# beovox-poe.net
KiCad netlist of a schematic drawn in Altium Designer
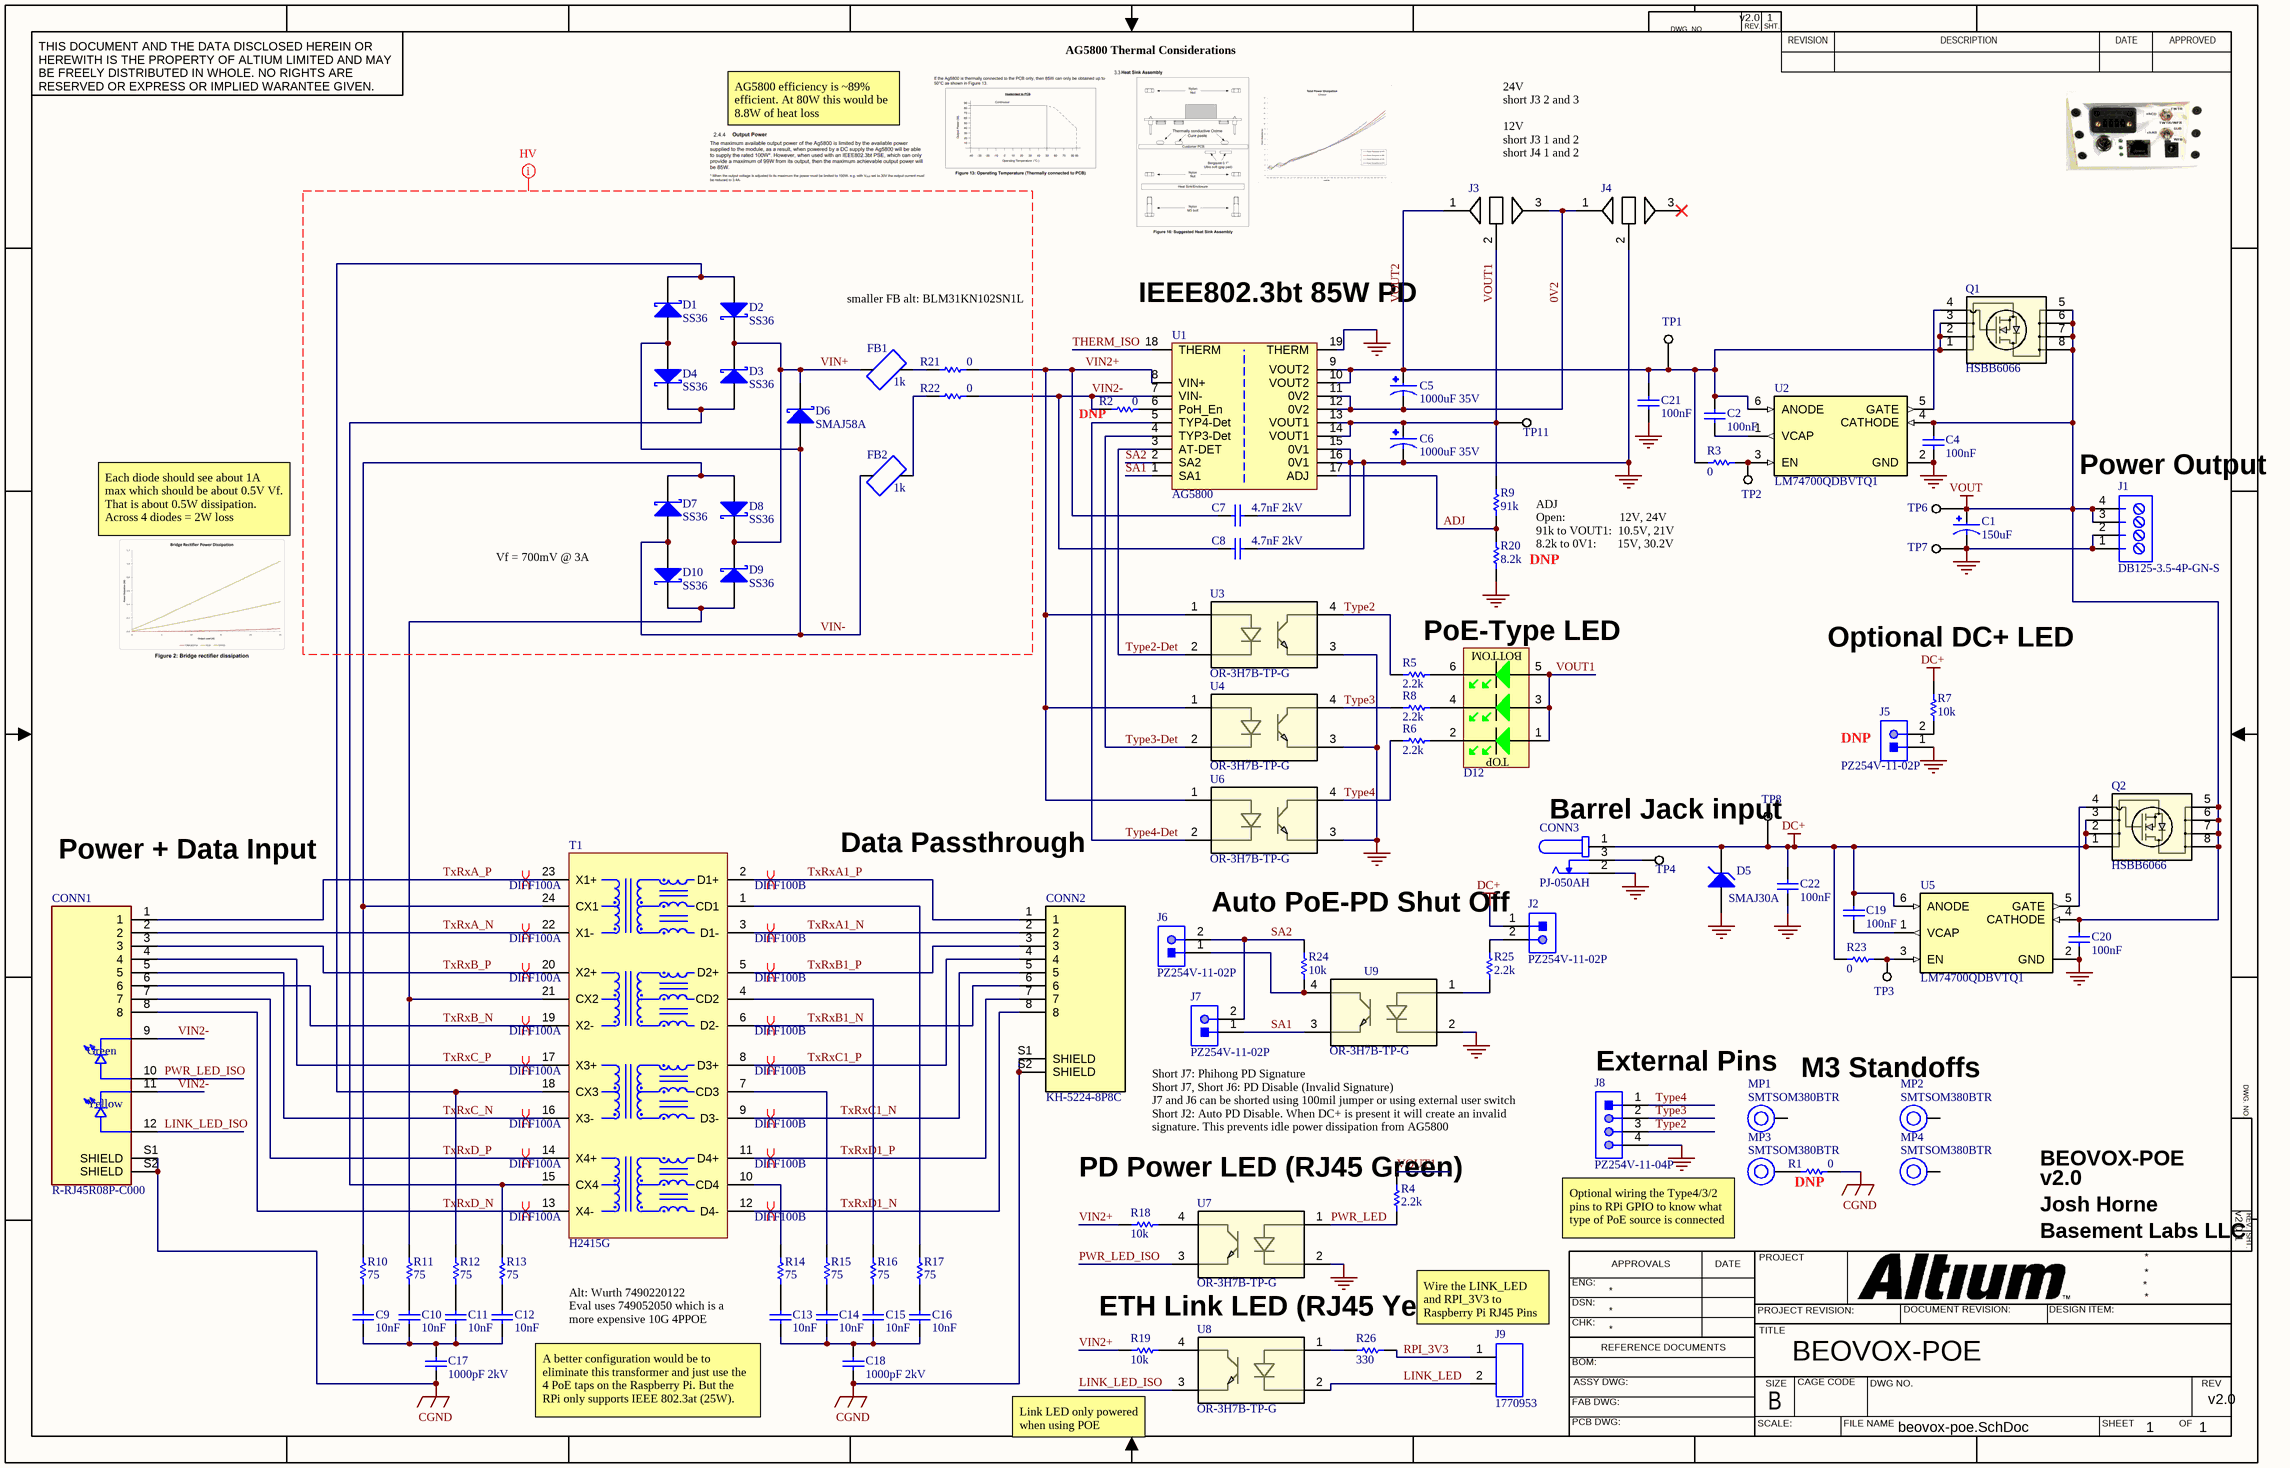
[diagram p0: beovox-poe.SchDoc]

(export (version "E")
  (design (tool "Eeschema 10.0.6"))
  (components
    (comp (ref "C1")
      (value "150uF")
      (footprint "CAP_CAN_10D_16H_THT")
      (description "150uF 80V Aluminum Electrolytic Capacitors Through Hole,D10xL16mm 3000hrs@105℃")
      (fields
        (field (name "MANUFACTURER") "BERYL Electronic Tech")
        (field (name "MANUFACTURER PART NUMBER") "RC080M151LO10*16TH-2A1Et")
      )
      (libsource (lib "josh-lib") (part "RC080M151LO10*16TH-2A1Et"))
    )
    (comp (ref "C2")
      (value "100nF")
      (footprint "CAP_0603_SK")
      (description "Multilayer Ceramic Capacitor, CC Series, 0.1 - F, - 10%, X7R, 50 V, 0603 [1608 Metric]")
      (fields
        (field (name "MANUFACTURER") "Yageo")
        (field (name "MANUFACTURER PART NUMBER") "CC0603KRX7R9BB104")
      )
      (libsource (lib "josh-lib") (part "C0603 100nF 50V X7R 10%"))
    )
    (comp (ref "C4")
      (value "100nF")
      (footprint "CAP_0603_SK")
      (description "Multilayer Ceramic Capacitor, CC Series, 0.1 - F, - 10%, X7R, 50 V, 0603 [1608 Metric]")
      (fields
        (field (name "MANUFACTURER") "Yageo")
        (field (name "MANUFACTURER PART NUMBER") "CC0603KRX7R9BB104")
      )
      (libsource (lib "josh-lib") (part "C0603 100nF 50V X7R 10%"))
    )
    (comp (ref "C5")
      (value "1000uF 35V")
      (footprint "CAP_TH_5_10X20")
      (description "1000uF 35V ±20% Plugin,D10xL20mm Aluminum Electrolytic Capacitors - Leaded ROHS")
      (fields
        (field (name "MANUFACTURER") "AISHI")
        (field (name "MANUFACTURER PART NUMBER") "ERR1VM102G20OT")
      )
      (libsource (lib "josh-lib") (part "ERR1VM102G20OT"))
    )
    (comp (ref "C6")
      (value "1000uF 35V")
      (footprint "CAP_TH_5_10X20")
      (description "1000uF 35V ±20% Plugin,D10xL20mm Aluminum Electrolytic Capacitors - Leaded ROHS")
      (fields
        (field (name "MANUFACTURER") "AISHI")
        (field (name "MANUFACTURER PART NUMBER") "ERR1VM102G20OT")
      )
      (libsource (lib "josh-lib") (part "ERR1VM102G20OT"))
    )
    (comp (ref "C7")
      (value "4.7nF 2kV")
      (footprint "CAP_1206_SK")
      (description "2kV 4700pF X7R ±10% 1206 Multilayer Ceramic Capacitors MLCC - SMD/SMT ROHS")
      (fields
        (field (name "MANUFACTURER") "FH (Guangdong Fenghua Advanced Tech)")
        (field (name "MANUFACTURER PART NUMBER") "1206B472K202NT")
      )
      (libsource (lib "josh-lib") (part "1206B472K202NT"))
    )
    (comp (ref "C8")
      (value "4.7nF 2kV")
      (footprint "CAP_1206_SK")
      (description "2kV 4700pF X7R ±10% 1206 Multilayer Ceramic Capacitors MLCC - SMD/SMT ROHS")
      (fields
        (field (name "MANUFACTURER") "FH (Guangdong Fenghua Advanced Tech)")
        (field (name "MANUFACTURER PART NUMBER") "1206B472K202NT")
      )
      (libsource (lib "josh-lib") (part "1206B472K202NT"))
    )
    (comp (ref "C9")
      (value "10nF")
      (footprint "CAP_0603_SK")
      (description "Multilayer Ceramic Capacitor, 0.01 F, 10%, X7R, 100 V, 0603 [1608 Metric] Rohs Compliant: Yes")
      (fields
        (field (name "MANUFACTURER") "Walsin Technologies")
        (field (name "MANUFACTURER PART NUMBER") "0603B103K101CT")
      )
      (libsource (lib "josh-lib") (part "0603B103K101CT"))
    )
    (comp (ref "C10")
      (value "10nF")
      (footprint "CAP_0603_SK")
      (description "Multilayer Ceramic Capacitor, 0.01 F, 10%, X7R, 100 V, 0603 [1608 Metric] Rohs Compliant: Yes")
      (fields
        (field (name "MANUFACTURER") "Walsin Technologies")
        (field (name "MANUFACTURER PART NUMBER") "0603B103K101CT")
      )
      (libsource (lib "josh-lib") (part "0603B103K101CT"))
    )
    (comp (ref "C11")
      (value "10nF")
      (footprint "CAP_0603_SK")
      (description "Multilayer Ceramic Capacitor, 0.01 F, 10%, X7R, 100 V, 0603 [1608 Metric] Rohs Compliant: Yes")
      (fields
        (field (name "MANUFACTURER") "Walsin Technologies")
        (field (name "MANUFACTURER PART NUMBER") "0603B103K101CT")
      )
      (libsource (lib "josh-lib") (part "0603B103K101CT"))
    )
    (comp (ref "C12")
      (value "10nF")
      (footprint "CAP_0603_SK")
      (description "Multilayer Ceramic Capacitor, 0.01 F, 10%, X7R, 100 V, 0603 [1608 Metric] Rohs Compliant: Yes")
      (fields
        (field (name "MANUFACTURER") "Walsin Technologies")
        (field (name "MANUFACTURER PART NUMBER") "0603B103K101CT")
      )
      (libsource (lib "josh-lib") (part "0603B103K101CT"))
    )
    (comp (ref "C13")
      (value "10nF")
      (footprint "CAP_0603_SK")
      (description "Multilayer Ceramic Capacitor, 0.01 F, 10%, X7R, 100 V, 0603 [1608 Metric] Rohs Compliant: Yes")
      (fields
        (field (name "MANUFACTURER") "Walsin Technologies")
        (field (name "MANUFACTURER PART NUMBER") "0603B103K101CT")
      )
      (libsource (lib "josh-lib") (part "0603B103K101CT"))
    )
    (comp (ref "C14")
      (value "10nF")
      (footprint "CAP_0603_SK")
      (description "Multilayer Ceramic Capacitor, 0.01 F, 10%, X7R, 100 V, 0603 [1608 Metric] Rohs Compliant: Yes")
      (fields
        (field (name "MANUFACTURER") "Walsin Technologies")
        (field (name "MANUFACTURER PART NUMBER") "0603B103K101CT")
      )
      (libsource (lib "josh-lib") (part "0603B103K101CT"))
    )
    (comp (ref "C15")
      (value "10nF")
      (footprint "CAP_0603_SK")
      (description "Multilayer Ceramic Capacitor, 0.01 F, 10%, X7R, 100 V, 0603 [1608 Metric] Rohs Compliant: Yes")
      (fields
        (field (name "MANUFACTURER") "Walsin Technologies")
        (field (name "MANUFACTURER PART NUMBER") "0603B103K101CT")
      )
      (libsource (lib "josh-lib") (part "0603B103K101CT"))
    )
    (comp (ref "C16")
      (value "10nF")
      (footprint "CAP_0603_SK")
      (description "Multilayer Ceramic Capacitor, 0.01 F, 10%, X7R, 100 V, 0603 [1608 Metric] Rohs Compliant: Yes")
      (fields
        (field (name "MANUFACTURER") "Walsin Technologies")
        (field (name "MANUFACTURER PART NUMBER") "0603B103K101CT")
      )
      (libsource (lib "josh-lib") (part "0603B103K101CT"))
    )
    (comp (ref "C17")
      (value "1000pF 2kV")
      (footprint "CAP_1206_SK")
      (description "Multilayer Ceramic Capacitor, 1000 pF, 2000 V, ± 10%, X7R, 1206 [3216 Metric]")
      (fields
        (field (name "MANUFACTURER") "Yageo")
        (field (name "MANUFACTURER PART NUMBER") "CC1206KKX7RDBB102")
      )
      (libsource (lib "josh-lib") (part "CC1206KKX7RDBB102"))
    )
    (comp (ref "C18")
      (value "1000pF 2kV")
      (footprint "CAP_1206_SK")
      (description "Multilayer Ceramic Capacitor, 1000 pF, 2000 V, ± 10%, X7R, 1206 [3216 Metric]")
      (fields
        (field (name "MANUFACTURER") "Yageo")
        (field (name "MANUFACTURER PART NUMBER") "CC1206KKX7RDBB102")
      )
      (libsource (lib "josh-lib") (part "CC1206KKX7RDBB102"))
    )
    (comp (ref "C19")
      (value "100nF")
      (footprint "CAP_0603_SK")
      (description "Multilayer Ceramic Capacitor, CC Series, 0.1 - F, - 10%, X7R, 50 V, 0603 [1608 Metric]")
      (fields
        (field (name "MANUFACTURER") "Yageo")
        (field (name "MANUFACTURER PART NUMBER") "CC0603KRX7R9BB104")
      )
      (libsource (lib "josh-lib") (part "C0603 100nF 50V X7R 10%"))
    )
    (comp (ref "C20")
      (value "100nF")
      (footprint "CAP_0603_SK")
      (description "Multilayer Ceramic Capacitor, CC Series, 0.1 - F, - 10%, X7R, 50 V, 0603 [1608 Metric]")
      (fields
        (field (name "MANUFACTURER") "Yageo")
        (field (name "MANUFACTURER PART NUMBER") "CC0603KRX7R9BB104")
      )
      (libsource (lib "josh-lib") (part "C0603 100nF 50V X7R 10%"))
    )
    (comp (ref "C21")
      (value "100nF")
      (footprint "CAP_0603_SK")
      (description "Multilayer Ceramic Capacitor, CC Series, 0.1 - F, - 10%, X7R, 50 V, 0603 [1608 Metric]")
      (fields
        (field (name "MANUFACTURER") "Yageo")
        (field (name "MANUFACTURER PART NUMBER") "CC0603KRX7R9BB104")
      )
      (libsource (lib "josh-lib") (part "C0603 100nF 50V X7R 10%"))
    )
    (comp (ref "C22")
      (value "100nF")
      (footprint "CAP_0603_SK")
      (description "Multilayer Ceramic Capacitor, CC Series, 0.1 - F, - 10%, X7R, 50 V, 0603 [1608 Metric]")
      (fields
        (field (name "MANUFACTURER") "Yageo")
        (field (name "MANUFACTURER PART NUMBER") "CC0603KRX7R9BB104")
      )
      (libsource (lib "josh-lib") (part "C0603 100nF 50V X7R 10%"))
    )
    (comp (ref "CONN1")
      (value "R-RJ45R08P-C000")
      (footprint "R-RJ45R08P-C000")
      (fields (field (name "MANUFACTURER") "Ckmtw"))
      (libsource (lib "josh-lib") (part "R-RJ45R08P-C000"))
    )
    (comp (ref "CONN2")
      (value "KH-5224-8P8C")
      (footprint "CONN_RJ45_KH-5224-8P8C")
      (description "Jack Modular Connector RJ45 Through Hole Shielded")
      (fields (field (name "MANUFACTURER") "Kinghelm"))
      (libsource (lib "josh-lib") (part "KH-5224-8P8C"))
    )
    (comp (ref "CONN3")
      (value "PJ-050AH")
      (footprint "CUI_PJ-050AH")
      (description "2.0 x 6.0 mm, 5.0 A, Horizontal, Through Hole, Pick-n-Place Top, Dc Power Jack Connector")
      (fields (field (name "MANUFACTURER") "Same Sky"))
      (libsource (lib "josh-lib") (part "PJ-050AH"))
    )
    (comp (ref "D1")
      (value "SS36")
      (footprint "DIOD-SMA-2_V")
      (description "60V 700mV@3A 3A SMA(DO-214AC) Schottky Barrier Diodes (SBD) ROHS")
      (fields (field (name "MANUFACTURER") "MDD"))
      (libsource (lib "josh-lib") (part "SS36"))
    )
    (comp (ref "D2")
      (value "SS36")
      (footprint "DIOD-SMA-2_V")
      (description "60V 700mV@3A 3A SMA(DO-214AC) Schottky Barrier Diodes (SBD) ROHS")
      (fields (field (name "MANUFACTURER") "MDD"))
      (libsource (lib "josh-lib") (part "SS36"))
    )
    (comp (ref "D3")
      (value "SS36")
      (footprint "DIOD-SMA-2_V")
      (description "60V 700mV@3A 3A SMA(DO-214AC) Schottky Barrier Diodes (SBD) ROHS")
      (fields (field (name "MANUFACTURER") "MDD"))
      (libsource (lib "josh-lib") (part "SS36"))
    )
    (comp (ref "D4")
      (value "SS36")
      (footprint "DIOD-SMA-2_V")
      (description "60V 700mV@3A 3A SMA(DO-214AC) Schottky Barrier Diodes (SBD) ROHS")
      (fields (field (name "MANUFACTURER") "MDD"))
      (libsource (lib "josh-lib") (part "SS36"))
    )
    (comp (ref "D5")
      (value "SMAJ30A")
      (footprint "DIOD-B360A_V")
      (description "Diode TVS Single Uni-Dir 30V 400W 2-Pin SMA")
      (fields (field (name "MANUFACTURER") "Littelfuse"))
      (libsource (lib "josh-lib") (part "SMAJ30A"))
    )
    (comp (ref "D6")
      (value "SMAJ58A")
      (footprint "DIOD-SMA-2_V")
      (description "4.3A 400W 93.6V 64.4V 58V SMA(DO-214AC) TVS ROHS")
      (fields (field (name "MANUFACTURER") "GOODWORK"))
      (libsource (lib "josh-lib") (part "SMAJ58A"))
    )
    (comp (ref "D7")
      (value "SS36")
      (footprint "DIOD-SMA-2_V")
      (description "60V 700mV@3A 3A SMA(DO-214AC) Schottky Barrier Diodes (SBD) ROHS")
      (fields (field (name "MANUFACTURER") "MDD"))
      (libsource (lib "josh-lib") (part "SS36"))
    )
    (comp (ref "D8")
      (value "SS36")
      (footprint "DIOD-SMA-2_V")
      (description "60V 700mV@3A 3A SMA(DO-214AC) Schottky Barrier Diodes (SBD) ROHS")
      (fields (field (name "MANUFACTURER") "MDD"))
      (libsource (lib "josh-lib") (part "SS36"))
    )
    (comp (ref "D9")
      (value "SS36")
      (footprint "DIOD-SMA-2_V")
      (description "60V 700mV@3A 3A SMA(DO-214AC) Schottky Barrier Diodes (SBD) ROHS")
      (fields (field (name "MANUFACTURER") "MDD"))
      (libsource (lib "josh-lib") (part "SS36"))
    )
    (comp (ref "D10")
      (value "SS36")
      (footprint "DIOD-SMA-2_V")
      (description "60V 700mV@3A 3A SMA(DO-214AC) Schottky Barrier Diodes (SBD) ROHS")
      (fields (field (name "MANUFACTURER") "MDD"))
      (libsource (lib "josh-lib") (part "SS36"))
    )
    (comp (ref "D12")
      (value "3 Diode Vertical LED Green")
      (footprint "MHK33147CGBTD")
      (description "20mA 30mcd 雾状绿透镜 -40℃~+85℃ 568nm Green 60° 2.6V DIP-6-2.54mm Light Emitting Diodes (LED) ROHS")
      (fields
        (field (name "MANUFACTURER") "MEIHUA")
        (field (name "MANUFACTURER PART NUMBER") "MHK33147CGBTD")
      )
      (libsource (lib "josh-lib") (part "MHK33147CGBTD"))
    )
    (comp (ref "FB1")
      (value "1k")
      (footprint "FB_1810")
      (description "Ind Chip Bead Multi-Layer 1KOhm 30% 100MHz Ferrite 3A 1810 T/R")
      (fields
        (field (name "MANUFACTURER") "TAIYO YUDEN")
        (field (name "MANUFACTURER PART NUMBER") "FBMH4525HM102NTV")
      )
      (libsource (lib "josh-lib") (part "FBMH4525HM102NTV"))
    )
    (comp (ref "FB2")
      (value "1k")
      (footprint "FB_1810")
      (description "Ind Chip Bead Multi-Layer 1KOhm 30% 100MHz Ferrite 3A 1810 T/R")
      (fields
        (field (name "MANUFACTURER") "TAIYO YUDEN")
        (field (name "MANUFACTURER PART NUMBER") "FBMH4525HM102NTV")
      )
      (libsource (lib "josh-lib") (part "FBMH4525HM102NTV"))
    )
    (comp (ref "J1")
      (value "DB125-3.5-4P-GN-S")
      (footprint "DB125-3.5-4P-GN-S")
      (description "1x4P -40℃~+105℃ 13.5A 250V Green 16~28 Straight pin 3.5mm 1 1 4 Plugin,P=3.5mm Screw terminal ROHS")
      (fields (field (name "MANUFACTURER") "DIBO"))
      (libsource (lib "josh-lib") (part "DB125-3.5-4P-GN-S"))
    )
    (comp (ref "J2")
      (value "PZ254V-11-02P")
      (footprint "61300211121")
      (fields (field (name "MANUFACTURER") "XFCN"))
      (libsource (lib "") (part "PZ254V-11-02P_1"))
    )
    (comp (ref "J3")
      (value "JUMPER")
      (footprint "SOLDER_JUMPER_3 large")
      (libsource (lib "josh-lib") (part "Solder_Jumper_3"))
    )
    (comp (ref "J4")
      (value "JUMPER")
      (footprint "SOLDER_JUMPER_3 large")
      (libsource (lib "josh-lib") (part "Solder_Jumper_3"))
    )
    (comp (ref "J5")
      (value "PZ254V-11-02P")
      (footprint "61300211121")
      (fields (field (name "MANUFACTURER") "XFCN"))
      (libsource (lib "josh-lib") (part "PZ254V-11-02P"))
    )
    (comp (ref "J6")
      (value "PZ254V-11-02P")
      (footprint "61300211121")
      (fields (field (name "MANUFACTURER") "XFCN"))
      (libsource (lib "josh-lib") (part "PZ254V-11-02P"))
    )
    (comp (ref "J7")
      (value "PZ254V-11-02P")
      (footprint "61300211121")
      (fields (field (name "MANUFACTURER") "XFCN"))
      (libsource (lib "josh-lib") (part "PZ254V-11-02P"))
    )
    (comp (ref "J8")
      (value "PZ254V-11-04P")
      (footprint "HDR_MALE_1x4")
      (fields (field (name "MANUFACTURER") "XFCN"))
      (libsource (lib "josh-lib") (part "PZ254V-11-04P"))
    )
    (comp (ref "J9")
      (value "1770953")
      (footprint "1770953")
      (description "TERM BLK 2P TOP ENTRY 2.5MM PCB")
      (fields (field (name "MANUFACTURER") "Phoenix Contact") (field (name "VOLTAGE") "150V"))
      (libsource (lib "josh-lib") (part "1770953"))
    )
    (comp (ref "MP1")
      (value "SMTSOM380BTR")
      (footprint "SMTSOM380_PlatedScrew")
      (description "M3 Round Nut 8mm height")
      (fields (field (name "MANUFACTURER") "YIYUAN"))
      (libsource (lib "josh-lib") (part "SMTSOM380BTR"))
    )
    (comp (ref "MP2")
      (value "SMTSOM380BTR")
      (footprint "SMTSOM380_PlatedScrew")
      (description "M3 Round Nut 8mm height")
      (fields (field (name "MANUFACTURER") "YIYUAN"))
      (libsource (lib "josh-lib") (part "SMTSOM380BTR"))
    )
    (comp (ref "MP3")
      (value "SMTSOM380BTR")
      (footprint "SMTSOM380_PlatedScrew")
      (description "M3 Round Nut 8mm height")
      (fields (field (name "MANUFACTURER") "YIYUAN"))
      (libsource (lib "josh-lib") (part "SMTSOM380BTR"))
    )
    (comp (ref "MP4")
      (value "SMTSOM380BTR")
      (footprint "SMTSOM380_PlatedScrew")
      (description "M3 Round Nut 8mm height")
      (fields (field (name "MANUFACTURER") "YIYUAN"))
      (libsource (lib "josh-lib") (part "SMTSOM380BTR"))
    )
    (comp (ref "Q1")
      (value "HSBB6066")
      (footprint "PPAK3X3_GAS")
      (description "N-Channel 60V 60A 45W PRPAK3x3-8L")
      (fields (field (name "MANUFACTURER") "HUASHUO"))
      (libsource (lib "josh-lib") (part "HSBB6066"))
    )
    (comp (ref "Q2")
      (value "HSBB6066")
      (footprint "PPAK3X3_GAS")
      (description "N-Channel 60V 60A 45W PRPAK3x3-8L")
      (fields (field (name "MANUFACTURER") "HUASHUO"))
      (libsource (lib "josh-lib") (part "HSBB6066"))
    )
    (comp (ref "R1")
      (value "0")
      (footprint "RES_0805")
      (description "Surface Mount Thick Film Resistor, RC Series, 125 mW, - 5%, 150 V, 0805 [2012 Metric]")
      (fields
        (field (name "MANUFACTURER") "Yageo")
        (field (name "MANUFACTURER PART NUMBER") "RC0805JR-070RL")
      )
      (libsource (lib "josh-lib") (part "RC0805JR-070RL"))
    )
    (comp (ref "R2")
      (value "0")
      (footprint "RES_0603")
      (description "Thick Film Resistors - SMD RMC 0603 1/10W 1% T/R-5000")
      (fields
        (field (name "MANUFACTURER") "Royal Ohm")
        (field (name "MANUFACTURER PART NUMBER") "0603WAF0000T5E")
      )
      (libsource (lib "josh-lib") (part "R0603 0R 1% 100mW"))
    )
    (comp (ref "R3")
      (value "0")
      (footprint "RES_0603")
      (description "Thick Film Resistors - SMD RMC 0603 1/10W 1% T/R-5000")
      (fields
        (field (name "MANUFACTURER") "Royal Ohm")
        (field (name "MANUFACTURER PART NUMBER") "0603WAF0000T5E")
      )
      (libsource (lib "josh-lib") (part "R0603 0R 1% 100mW"))
    )
    (comp (ref "R4")
      (value "2.2k")
      (footprint "RES_0603")
      (description "Res Thick Film 0603 2.2K Ohm 1% 0.1W(1/10W) ±100ppm/C Pad SMD T/R")
      (fields
        (field (name "MANUFACTURER") "Royal Ohm")
        (field (name "MANUFACTURER PART NUMBER") "0603WAF2201T5E")
      )
      (libsource (lib "josh-lib") (part "R0603 2K2 1% 100mW"))
    )
    (comp (ref "R5")
      (value "2.2k")
      (footprint "RES_0603")
      (description "Res Thick Film 0603 2.2K Ohm 1% 0.1W(1/10W) ±100ppm/C Pad SMD T/R")
      (fields
        (field (name "MANUFACTURER") "Royal Ohm")
        (field (name "MANUFACTURER PART NUMBER") "0603WAF2201T5E")
      )
      (libsource (lib "josh-lib") (part "R0603 2K2 1% 100mW"))
    )
    (comp (ref "R6")
      (value "2.2k")
      (footprint "RES_0603")
      (description "Res Thick Film 0603 2.2K Ohm 1% 0.1W(1/10W) ±100ppm/C Pad SMD T/R")
      (fields
        (field (name "MANUFACTURER") "Royal Ohm")
        (field (name "MANUFACTURER PART NUMBER") "0603WAF2201T5E")
      )
      (libsource (lib "josh-lib") (part "R0603 2K2 1% 100mW"))
    )
    (comp (ref "R7")
      (value "10k")
      (footprint "RES_0603")
      (description "Res Thick Film 0603 10K Ohm 1% 0.1W(1/10W) ±100ppm/C Pad SMD")
      (fields
        (field (name "MANUFACTURER") "Royal Ohm")
        (field (name "MANUFACTURER PART NUMBER") "0603WAF1002T5E")
      )
      (libsource (lib "josh-lib") (part "R0603 10K 1% 100mW JLC"))
    )
    (comp (ref "R8")
      (value "2.2k")
      (footprint "RES_0603")
      (description "Res Thick Film 0603 2.2K Ohm 1% 0.1W(1/10W) ±100ppm/C Pad SMD T/R")
      (fields
        (field (name "MANUFACTURER") "Royal Ohm")
        (field (name "MANUFACTURER PART NUMBER") "0603WAF2201T5E")
      )
      (libsource (lib "josh-lib") (part "R0603 2K2 1% 100mW"))
    )
    (comp (ref "R9")
      (value "91k")
      (footprint "RES_0603")
      (description "SMD Chip Resistor, 91 kOhm, ± 1%, 100 mW, 0603 [1608 Metric], Thick Film, General Purpose")
      (fields
        (field (name "MANUFACTURER") "Yageo")
        (field (name "MANUFACTURER PART NUMBER") "RC0603FR-0791KL")
      )
      (libsource (lib "josh-lib") (part "RC0603FR-0791KL"))
    )
    (comp (ref "R10")
      (value "75")
      (footprint "RES_0603")
      (description "SMD Chip Resistor, 75 Ohm, ± 1%, 100 mW, 0603 [1608 Metric], Thick Film, General Purpose")
      (fields
        (field (name "MANUFACTURER") "Yageo")
        (field (name "MANUFACTURER PART NUMBER") "RC0603FR-0775RL")
      )
      (libsource (lib "josh-lib") (part "RC0603FR-0775RL"))
    )
    (comp (ref "R11")
      (value "75")
      (footprint "RES_0603")
      (description "SMD Chip Resistor, 75 Ohm, ± 1%, 100 mW, 0603 [1608 Metric], Thick Film, General Purpose")
      (fields
        (field (name "MANUFACTURER") "Yageo")
        (field (name "MANUFACTURER PART NUMBER") "RC0603FR-0775RL")
      )
      (libsource (lib "josh-lib") (part "RC0603FR-0775RL"))
    )
    (comp (ref "R12")
      (value "75")
      (footprint "RES_0603")
      (description "SMD Chip Resistor, 75 Ohm, ± 1%, 100 mW, 0603 [1608 Metric], Thick Film, General Purpose")
      (fields
        (field (name "MANUFACTURER") "Yageo")
        (field (name "MANUFACTURER PART NUMBER") "RC0603FR-0775RL")
      )
      (libsource (lib "josh-lib") (part "RC0603FR-0775RL"))
    )
    (comp (ref "R13")
      (value "75")
      (footprint "RES_0603")
      (description "SMD Chip Resistor, 75 Ohm, ± 1%, 100 mW, 0603 [1608 Metric], Thick Film, General Purpose")
      (fields
        (field (name "MANUFACTURER") "Yageo")
        (field (name "MANUFACTURER PART NUMBER") "RC0603FR-0775RL")
      )
      (libsource (lib "josh-lib") (part "RC0603FR-0775RL"))
    )
    (comp (ref "R14")
      (value "75")
      (footprint "RES_0603")
      (description "SMD Chip Resistor, 75 Ohm, ± 1%, 100 mW, 0603 [1608 Metric], Thick Film, General Purpose")
      (fields
        (field (name "MANUFACTURER") "Yageo")
        (field (name "MANUFACTURER PART NUMBER") "RC0603FR-0775RL")
      )
      (libsource (lib "josh-lib") (part "RC0603FR-0775RL"))
    )
    (comp (ref "R15")
      (value "75")
      (footprint "RES_0603")
      (description "SMD Chip Resistor, 75 Ohm, ± 1%, 100 mW, 0603 [1608 Metric], Thick Film, General Purpose")
      (fields
        (field (name "MANUFACTURER") "Yageo")
        (field (name "MANUFACTURER PART NUMBER") "RC0603FR-0775RL")
      )
      (libsource (lib "josh-lib") (part "RC0603FR-0775RL"))
    )
    (comp (ref "R16")
      (value "75")
      (footprint "RES_0603")
      (description "SMD Chip Resistor, 75 Ohm, ± 1%, 100 mW, 0603 [1608 Metric], Thick Film, General Purpose")
      (fields
        (field (name "MANUFACTURER") "Yageo")
        (field (name "MANUFACTURER PART NUMBER") "RC0603FR-0775RL")
      )
      (libsource (lib "josh-lib") (part "RC0603FR-0775RL"))
    )
    (comp (ref "R17")
      (value "75")
      (footprint "RES_0603")
      (description "SMD Chip Resistor, 75 Ohm, ± 1%, 100 mW, 0603 [1608 Metric], Thick Film, General Purpose")
      (fields
        (field (name "MANUFACTURER") "Yageo")
        (field (name "MANUFACTURER PART NUMBER") "RC0603FR-0775RL")
      )
      (libsource (lib "josh-lib") (part "RC0603FR-0775RL"))
    )
    (comp (ref "R18")
      (value "10k")
      (footprint "RES_0603")
      (description "Res Thick Film 0603 10K Ohm 1% 0.1W(1/10W) ±100ppm/C Pad SMD")
      (fields
        (field (name "MANUFACTURER") "Royal Ohm")
        (field (name "MANUFACTURER PART NUMBER") "0603WAF1002T5E")
      )
      (libsource (lib "josh-lib") (part "R0603 10K 1% 100mW JLC"))
    )
    (comp (ref "R19")
      (value "10k")
      (footprint "RES_0603")
      (description "Res Thick Film 0603 10K Ohm 1% 0.1W(1/10W) ±100ppm/C Pad SMD")
      (fields
        (field (name "MANUFACTURER") "Royal Ohm")
        (field (name "MANUFACTURER PART NUMBER") "0603WAF1002T5E")
      )
      (libsource (lib "josh-lib") (part "R0603 10K 1% 100mW JLC"))
    )
    (comp (ref "R20")
      (value "8.2k")
      (footprint "RES_0603")
      (description "Res Thick Film 0603 8.2K Ohm 1% 0.1W(1/10W) ±100ppm/C Pad SMD T/R")
      (fields
        (field (name "MANUFACTURER") "Yageo")
        (field (name "MANUFACTURER PART NUMBER") "RC0603FR-078K2L")
      )
      (libsource (lib "josh-lib") (part "RC0603FR-078K2L"))
    )
    (comp (ref "R21")
      (value "0")
      (footprint "RES_1812")
      (description "-55℃~+155℃ 0Ω 1W 200V Thick Film Resistor ±5% 1812 Chip Resistor - Surface Mount ROHS")
      (fields
        (field (name "MANUFACTURER") "FOJAN")
        (field (name "MANUFACTURER PART NUMBER") "FRC1812F0000TS")
      )
      (libsource (lib "josh-lib") (part "R1812 0R 1% 750mW"))
    )
    (comp (ref "R22")
      (value "0")
      (footprint "RES_1812")
      (description "-55℃~+155℃ 0Ω 1W 200V Thick Film Resistor ±5% 1812 Chip Resistor - Surface Mount ROHS")
      (fields
        (field (name "MANUFACTURER") "FOJAN")
        (field (name "MANUFACTURER PART NUMBER") "FRC1812F0000TS")
      )
      (libsource (lib "josh-lib") (part "R1812 0R 1% 750mW"))
    )
    (comp (ref "R23")
      (value "0")
      (footprint "RES_0603")
      (description "Thick Film Resistors - SMD RMC 0603 1/10W 1% T/R-5000")
      (fields
        (field (name "MANUFACTURER") "Royal Ohm")
        (field (name "MANUFACTURER PART NUMBER") "0603WAF0000T5E")
      )
      (libsource (lib "josh-lib") (part "R0603 0R 1% 100mW"))
    )
    (comp (ref "R24")
      (value "10k")
      (footprint "RES_0603")
      (description "Res Thick Film 0603 10K Ohm 1% 0.1W(1/10W) ±100ppm/C Pad SMD")
      (fields
        (field (name "MANUFACTURER") "Royal Ohm")
        (field (name "MANUFACTURER PART NUMBER") "0603WAF1002T5E")
      )
      (libsource (lib "josh-lib") (part "R0603 10K 1% 100mW JLC"))
    )
    (comp (ref "R25")
      (value "2.2k")
      (footprint "RES_0603")
      (description "Res Thick Film 0603 2.2K Ohm 1% 0.1W(1/10W) ±100ppm/C Pad SMD T/R")
      (fields
        (field (name "MANUFACTURER") "Royal Ohm")
        (field (name "MANUFACTURER PART NUMBER") "0603WAF2201T5E")
      )
      (libsource (lib "josh-lib") (part "R0603 2K2 1% 100mW"))
    )
    (comp (ref "R26")
      (value "330")
      (footprint "RES_0603")
      (fields
        (field (name "MANUFACTURER") "Royal Ohm")
        (field (name "MANUFACTURER PART NUMBER") "0603WAF3300T5E")
        (field (name "TOLERANCE") "1%")
      )
      (libsource (lib "josh-lib") (part "R0603 330R 1% 100mW"))
    )
    (comp (ref "T1")
      (value "H2415G")
      (footprint "XFMR_H2415G")
      (description "LAN Transformer 1:1 Surface Mount IEEE 802.3bt")
      (fields (field (name "MANUFACTURER") "E-NETTR"))
      (libsource (lib "josh-lib") (part "H2415G"))
    )
    (comp (ref "TP1") (value "TP") (footprint "Test_Point") (libsource (lib "josh-lib") (part "Test_Point")))
    (comp (ref "TP2") (value "TP") (footprint "Test_Point") (libsource (lib "") (part "Test_Point_1")))
    (comp (ref "TP3") (value "TP") (footprint "Test_Point") (libsource (lib "") (part "Test_Point_1")))
    (comp (ref "TP4") (value "TP") (footprint "Test_Point") (libsource (lib "") (part "Test_Point_1")))
    (comp (ref "TP6") (value "TP") (footprint "Test_Point") (libsource (lib "josh-lib") (part "Test_Point")))
    (comp (ref "TP7") (value "TP") (footprint "Test_Point") (libsource (lib "josh-lib") (part "Test_Point")))
    (comp (ref "TP8") (value "TP") (footprint "Test_Point") (libsource (lib "josh-lib") (part "Test_Point")))
    (comp (ref "TP11") (value "TP") (footprint "Test_Point") (libsource (lib "josh-lib") (part "Test_Point")))
    (comp (ref "U1")
      (value "AG5800")
      (footprint "AG5800")
      (description "IEEE802.3bt 4-Pair PD Module - works with AG6800")
      (fields (field (name "MANUFACTURER") "Silvertel"))
      (libsource (lib "josh-lib") (part "AG5800"))
    )
    (comp (ref "U2")
      (value "LM74700QDBVTQ1")
      (footprint "SOT95P280X145-6N")
      (description "Low IQ Reverse Battery Protection Ideal Diode Controller 3.2V to 65V 6-Pin SOT-23 T/R")
      (fields (field (name "MANUFACTURER") "Texas Instruments"))
      (libsource (lib "josh-lib") (part "LM74700QDBVTQ1"))
    )
    (comp (ref "U3")
      (value "OR-3H7B-TP-G")
      (footprint "SOIC_(B)(TA)-VG_EVS")
      (description "80V 3750V 50mA 0.4V@2.4mA,8mA 1 6V 1.2V DC SOP-4-1.27mm Optocouplers - Phototransistor Output ROHS")
      (fields (field (name "MANUFACTURER") "Orient"))
      (libsource (lib "josh-lib") (part "OR-3H7B-TP-G"))
    )
    (comp (ref "U4")
      (value "OR-3H7B-TP-G")
      (footprint "SOIC_(B)(TA)-VG_EVS")
      (description "80V 3750V 50mA 0.4V@2.4mA,8mA 1 6V 1.2V DC SOP-4-1.27mm Optocouplers - Phototransistor Output ROHS")
      (fields (field (name "MANUFACTURER") "Orient"))
      (libsource (lib "josh-lib") (part "OR-3H7B-TP-G"))
    )
    (comp (ref "U5")
      (value "LM74700QDBVTQ1")
      (footprint "SOT95P280X145-6N")
      (description "Low IQ Reverse Battery Protection Ideal Diode Controller 3.2V to 65V 6-Pin SOT-23 T/R")
      (fields (field (name "MANUFACTURER") "Texas Instruments"))
      (libsource (lib "josh-lib") (part "LM74700QDBVTQ1"))
    )
    (comp (ref "U6")
      (value "OR-3H7B-TP-G")
      (footprint "SOIC_(B)(TA)-VG_EVS")
      (description "80V 3750V 50mA 0.4V@2.4mA,8mA 1 6V 1.2V DC SOP-4-1.27mm Optocouplers - Phototransistor Output ROHS")
      (fields (field (name "MANUFACTURER") "Orient"))
      (libsource (lib "josh-lib") (part "OR-3H7B-TP-G"))
    )
    (comp (ref "U7")
      (value "OR-3H7B-TP-G")
      (footprint "SOIC_(B)(TA)-VG_EVS")
      (description "80V 3750V 50mA 0.4V@2.4mA,8mA 1 6V 1.2V DC SOP-4-1.27mm Optocouplers - Phototransistor Output ROHS")
      (fields (field (name "MANUFACTURER") "Orient"))
      (libsource (lib "") (part "OR-3H7B-TP-G_1"))
    )
    (comp (ref "U8")
      (value "OR-3H7B-TP-G")
      (footprint "SOIC_(B)(TA)-VG_EVS")
      (description "80V 3750V 50mA 0.4V@2.4mA,8mA 1 6V 1.2V DC SOP-4-1.27mm Optocouplers - Phototransistor Output ROHS")
      (fields (field (name "MANUFACTURER") "Orient"))
      (libsource (lib "") (part "OR-3H7B-TP-G_1"))
    )
    (comp (ref "U9")
      (value "OR-3H7B-TP-G")
      (footprint "SOIC_(B)(TA)-VG_EVS")
      (description "80V 3750V 50mA 0.4V@2.4mA,8mA 1 6V 1.2V DC SOP-4-1.27mm Optocouplers - Phototransistor Output ROHS")
      (fields (field (name "MANUFACTURER") "Orient"))
      (libsource (lib "") (part "OR-3H7B-TP-G_1"))
    )
  )
  (nets
    (net (code "1") (name "/0V2") (class "Default")
      (node (ref "C5") (pin "N") (pinfunction "N_N") (pintype "passive"))
      (node (ref "J3") (pin "3") (pinfunction "3_3") (pintype "passive"))
      (node (ref "J4") (pin "1") (pinfunction "1_1") (pintype "passive"))
      (node (ref "U1") (pin "11") (pinfunction "0V2_11") (pintype "passive"))
      (node (ref "U1") (pin "12") (pinfunction "0V2_12") (pintype "passive"))
    )
    (net (code "2") (name "/ADJ") (class "Default")
      (node (ref "R20") (pin "2") (pinfunction "2_2") (pintype "passive"))
      (node (ref "R9") (pin "2") (pinfunction "2_2") (pintype "passive"))
      (node (ref "U1") (pin "17") (pinfunction "ADJ_17") (pintype "passive"))
    )
    (net (code "3") (name "/LINK_LED") (class "Default")
      (node (ref "J9") (pin "2") (pinfunction "2_2") (pintype "passive"))
      (node (ref "U8") (pin "2") (pinfunction "2_2") (pintype "passive"))
    )
    (net (code "4") (name "/LINK_LED_ISO") (class "Default")
      (node (ref "CONN1") (pin "12") (pinfunction "12_12") (pintype "passive"))
      (node (ref "U8") (pin "3") (pinfunction "3_3") (pintype "passive"))
    )
    (net (code "5") (name "/PWR_LED") (class "Default")
      (node (ref "R4") (pin "1") (pinfunction "1_1") (pintype "passive"))
      (node (ref "U7") (pin "1") (pinfunction "1_1") (pintype "passive"))
    )
    (net (code "6") (name "/PWR_LED_ISO") (class "Default")
      (node (ref "CONN1") (pin "10") (pinfunction "10_10") (pintype "passive"))
      (node (ref "U7") (pin "3") (pinfunction "3_3") (pintype "passive"))
    )
    (net (code "7") (name "/RPI_3V3") (class "Default")
      (node (ref "J9") (pin "1") (pinfunction "1_1") (pintype "passive"))
      (node (ref "R26") (pin "2") (pinfunction "2_2") (pintype "passive"))
    )
    (net (code "8") (name "/SA1") (class "Default")
      (node (ref "J7") (pin "1") (pinfunction "1_1") (pintype "passive"))
      (node (ref "U1") (pin "1") (pinfunction "SA1_1") (pintype "passive"))
      (node (ref "U9") (pin "3") (pinfunction "3_3") (pintype "passive"))
    )
    (net (code "9") (name "/SA2") (class "Default")
      (node (ref "J6") (pin "2") (pinfunction "2_2") (pintype "passive"))
      (node (ref "J7") (pin "2") (pinfunction "2_2") (pintype "passive"))
      (node (ref "R24") (pin "2") (pinfunction "2_2") (pintype "passive"))
      (node (ref "U1") (pin "2") (pinfunction "SA2_2") (pintype "passive"))
    )
    (net (code "10") (name "/THERM_ISO") (class "Default")
      (node (ref "U1") (pin "18") (pinfunction "THERM_18") (pintype "passive"))
    )
    (net (code "11") (name "/TxRxA1_N") (class "Default")
      (node (ref "CONN2") (pin "2") (pinfunction "2_2") (pintype "passive"))
      (node (ref "T1") (pin "3") (pinfunction "D1-_3") (pintype "passive"))
    )
    (net (code "12") (name "/TxRxA1_P") (class "Default")
      (node (ref "CONN2") (pin "1") (pinfunction "1_1") (pintype "passive"))
      (node (ref "T1") (pin "2") (pinfunction "D1+_2") (pintype "passive"))
    )
    (net (code "13") (name "/TxRxA_N") (class "Default")
      (node (ref "CONN1") (pin "2") (pinfunction "2_2") (pintype "passive"))
      (node (ref "T1") (pin "22") (pinfunction "X1-_22") (pintype "passive"))
    )
    (net (code "14") (name "/TxRxA_P") (class "Default")
      (node (ref "CONN1") (pin "1") (pinfunction "1_1") (pintype "passive"))
      (node (ref "T1") (pin "23") (pinfunction "X1+_23") (pintype "passive"))
    )
    (net (code "15") (name "/TxRxB1_N") (class "Default")
      (node (ref "CONN2") (pin "6") (pinfunction "6_6") (pintype "passive"))
      (node (ref "T1") (pin "6") (pinfunction "D2-_6") (pintype "passive"))
    )
    (net (code "16") (name "/TxRxB1_P") (class "Default")
      (node (ref "CONN2") (pin "3") (pinfunction "3_3") (pintype "passive"))
      (node (ref "T1") (pin "5") (pinfunction "D2+_5") (pintype "passive"))
    )
    (net (code "17") (name "/TxRxB_N") (class "Default")
      (node (ref "CONN1") (pin "6") (pinfunction "6_6") (pintype "passive"))
      (node (ref "T1") (pin "19") (pinfunction "X2-_19") (pintype "passive"))
    )
    (net (code "18") (name "/TxRxB_P") (class "Default")
      (node (ref "CONN1") (pin "3") (pinfunction "3_3") (pintype "passive"))
      (node (ref "T1") (pin "20") (pinfunction "X2+_20") (pintype "passive"))
    )
    (net (code "19") (name "/TxRxC1_N") (class "Default")
      (node (ref "CONN2") (pin "5") (pinfunction "5_5") (pintype "passive"))
      (node (ref "T1") (pin "9") (pinfunction "D3-_9") (pintype "passive"))
    )
    (net (code "20") (name "/TxRxC1_P") (class "Default")
      (node (ref "CONN2") (pin "4") (pinfunction "4_4") (pintype "passive"))
      (node (ref "T1") (pin "8") (pinfunction "D3+_8") (pintype "passive"))
    )
    (net (code "21") (name "/TxRxC_N") (class "Default")
      (node (ref "CONN1") (pin "5") (pinfunction "5_5") (pintype "passive"))
      (node (ref "T1") (pin "16") (pinfunction "X3-_16") (pintype "passive"))
    )
    (net (code "22") (name "/TxRxC_P") (class "Default")
      (node (ref "CONN1") (pin "4") (pinfunction "4_4") (pintype "passive"))
      (node (ref "T1") (pin "17") (pinfunction "X3+_17") (pintype "passive"))
    )
    (net (code "23") (name "/TxRxD1_N") (class "Default")
      (node (ref "CONN2") (pin "8") (pinfunction "8_8") (pintype "passive"))
      (node (ref "T1") (pin "12") (pinfunction "D4-_12") (pintype "passive"))
    )
    (net (code "24") (name "/TxRxD1_P") (class "Default")
      (node (ref "CONN2") (pin "7") (pinfunction "7_7") (pintype "passive"))
      (node (ref "T1") (pin "11") (pinfunction "D4+_11") (pintype "passive"))
    )
    (net (code "25") (name "/TxRxD_N") (class "Default")
      (node (ref "CONN1") (pin "8") (pinfunction "8_8") (pintype "passive"))
      (node (ref "T1") (pin "13") (pinfunction "X4-_13") (pintype "passive"))
    )
    (net (code "26") (name "/TxRxD_P") (class "Default")
      (node (ref "CONN1") (pin "7") (pinfunction "7_7") (pintype "passive"))
      (node (ref "T1") (pin "14") (pinfunction "X4+_14") (pintype "passive"))
    )
    (net (code "27") (name "/Type2") (class "Default")
      (node (ref "J8") (pin "3") (pinfunction "3_3") (pintype "passive"))
      (node (ref "R5") (pin "2") (pinfunction "2_2") (pintype "passive"))
      (node (ref "U3") (pin "4") (pinfunction "4_4") (pintype "passive"))
    )
    (net (code "28") (name "/Type2-Det") (class "Default")
      (node (ref "U1") (pin "3") (pinfunction "AT-DET_3") (pintype "passive"))
      (node (ref "U3") (pin "2") (pinfunction "2_2") (pintype "passive"))
    )
    (net (code "29") (name "/Type3") (class "Default")
      (node (ref "J8") (pin "2") (pinfunction "2_2") (pintype "passive"))
      (node (ref "R8") (pin "2") (pinfunction "2_2") (pintype "passive"))
      (node (ref "U4") (pin "4") (pinfunction "4_4") (pintype "passive"))
    )
    (net (code "30") (name "/Type3-Det") (class "Default")
      (node (ref "U1") (pin "4") (pinfunction "TYP3-Det_4") (pintype "passive"))
      (node (ref "U4") (pin "2") (pinfunction "2_2") (pintype "passive"))
    )
    (net (code "31") (name "/Type4") (class "Default")
      (node (ref "J8") (pin "1") (pinfunction "1_1") (pintype "passive"))
      (node (ref "R6") (pin "2") (pinfunction "2_2") (pintype "passive"))
      (node (ref "U6") (pin "4") (pinfunction "4_4") (pintype "passive"))
    )
    (net (code "32") (name "/Type4-Det") (class "Default")
      (node (ref "U1") (pin "5") (pinfunction "TYP4-Det_5") (pintype "passive"))
      (node (ref "U6") (pin "2") (pinfunction "2_2") (pintype "passive"))
    )
    (net (code "33") (name "/VIN+") (class "Default")
      (node (ref "D2") (pin "2") (pinfunction "K_2") (pintype "passive"))
      (node (ref "D3") (pin "2") (pinfunction "K_2") (pintype "passive"))
      (node (ref "D6") (pin "2") (pinfunction "K_2") (pintype "passive"))
      (node (ref "D8") (pin "2") (pinfunction "K_2") (pintype "passive"))
      (node (ref "D9") (pin "2") (pinfunction "K_2") (pintype "passive"))
      (node (ref "FB1") (pin "1") (pinfunction "1_1") (pintype "passive"))
    )
    (net (code "34") (name "/VIN-") (class "Default")
      (node (ref "D1") (pin "1") (pinfunction "A_1") (pintype "passive"))
      (node (ref "D10") (pin "1") (pinfunction "A_1") (pintype "passive"))
      (node (ref "D4") (pin "1") (pinfunction "A_1") (pintype "passive"))
      (node (ref "D6") (pin "1") (pinfunction "A_1") (pintype "passive"))
      (node (ref "D7") (pin "1") (pinfunction "A_1") (pintype "passive"))
      (node (ref "FB2") (pin "1") (pinfunction "1_1") (pintype "passive"))
    )
    (net (code "35") (name "/VIN2+") (class "Default")
      (node (ref "C7") (pin "1") (pinfunction "1_1") (pintype "passive"))
      (node (ref "R18") (pin "2") (pinfunction "2_2") (pintype "passive"))
      (node (ref "R19") (pin "2") (pinfunction "2_2") (pintype "passive"))
      (node (ref "R21") (pin "2") (pinfunction "2_2") (pintype "passive"))
      (node (ref "U1") (pin "8") (pinfunction "VIN+_8") (pintype "passive"))
      (node (ref "U3") (pin "1") (pinfunction "1_1") (pintype "passive"))
      (node (ref "U4") (pin "1") (pinfunction "1_1") (pintype "passive"))
      (node (ref "U6") (pin "1") (pinfunction "1_1") (pintype "passive"))
    )
    (net (code "36") (name "/VIN2-") (class "Default")
      (node (ref "C8") (pin "1") (pinfunction "1_1") (pintype "passive"))
      (node (ref "CONN1") (pin "11") (pinfunction "11_11") (pintype "passive"))
      (node (ref "CONN1") (pin "9") (pinfunction "9_9") (pintype "passive"))
      (node (ref "R2") (pin "2") (pinfunction "2_2") (pintype "passive"))
      (node (ref "R22") (pin "2") (pinfunction "2_2") (pintype "passive"))
      (node (ref "U1") (pin "7") (pinfunction "VIN-_7") (pintype "passive"))
    )
    (net (code "37") (name "/VOUT1") (class "Default")
      (node (ref "C6") (pin "P") (pinfunction "P_P") (pintype "passive"))
      (node (ref "D12") (pin "1") (pinfunction "1_1") (pintype "passive"))
      (node (ref "D12") (pin "3") (pinfunction "3_3") (pintype "passive"))
      (node (ref "D12") (pin "5") (pinfunction "5_5") (pintype "passive"))
      (node (ref "J3") (pin "2") (pinfunction "2_2") (pintype "passive"))
      (node (ref "R4") (pin "2") (pinfunction "2_2") (pintype "passive"))
      (node (ref "R9") (pin "1") (pinfunction "1_1") (pintype "passive"))
      (node (ref "TP11") (pin "1") (pinfunction "1_1") (pintype "passive"))
      (node (ref "U1") (pin "13") (pinfunction "VOUT1_13") (pintype "passive"))
      (node (ref "U1") (pin "14") (pinfunction "VOUT1_14") (pintype "passive"))
    )
    (net (code "38") (name "/VOUT2") (class "Default")
      (node (ref "C2") (pin "2") (pinfunction "2_2") (pintype "passive"))
      (node (ref "C21") (pin "2") (pinfunction "2_2") (pintype "passive"))
      (node (ref "C5") (pin "P") (pinfunction "P_P") (pintype "passive"))
      (node (ref "J3") (pin "1") (pinfunction "1_1") (pintype "passive"))
      (node (ref "Q1") (pin "1") (pinfunction "1_1") (pintype "passive"))
      (node (ref "Q1") (pin "2") (pinfunction "2_2") (pintype "passive"))
      (node (ref "Q1") (pin "3") (pinfunction "3_3") (pintype "passive"))
      (node (ref "R3") (pin "2") (pinfunction "2_2") (pintype "passive"))
      (node (ref "TP1") (pin "1") (pinfunction "1_1") (pintype "passive"))
      (node (ref "U1") (pin "10") (pinfunction "VOUT2_10") (pintype "passive"))
      (node (ref "U1") (pin "9") (pinfunction "VOUT2_9") (pintype "passive"))
      (node (ref "U2") (pin "6") (pinfunction "ANODE_6") (pintype "input"))
    )
    (net (code "39") (name "CGND") (class "Default")
      (node (ref "C17") (pin "1") (pinfunction "1_1") (pintype "passive"))
      (node (ref "C18") (pin "1") (pinfunction "1_1") (pintype "passive"))
      (node (ref "CONN1") (pin "S1") (pinfunction "SHIELD_S1") (pintype "passive"))
      (node (ref "CONN1") (pin "S2") (pinfunction "SHIELD_S2") (pintype "passive"))
      (node (ref "CONN2") (pin "S1") (pinfunction "SHIELD_S1") (pintype "passive"))
      (node (ref "CONN2") (pin "S2") (pinfunction "SHIELD_S2") (pintype "passive"))
      (node (ref "R1") (pin "2") (pinfunction "2_2") (pintype "passive"))
    )
    (net (code "40") (name "DC+") (class "Default")
      (node (ref "C19") (pin "2") (pinfunction "2_2") (pintype "passive"))
      (node (ref "C22") (pin "2") (pinfunction "2_2") (pintype "passive"))
      (node (ref "CONN3") (pin "1") (pinfunction "1_1") (pintype "passive"))
      (node (ref "D5") (pin "2") (pinfunction "K_2") (pintype "passive"))
      (node (ref "J2") (pin "1") (pinfunction "1_1") (pintype "passive"))
      (node (ref "Q2") (pin "1") (pinfunction "1_1") (pintype "passive"))
      (node (ref "Q2") (pin "2") (pinfunction "2_2") (pintype "passive"))
      (node (ref "Q2") (pin "3") (pinfunction "3_3") (pintype "passive"))
      (node (ref "R23") (pin "2") (pinfunction "2_2") (pintype "passive"))
      (node (ref "R7") (pin "1") (pinfunction "1_1") (pintype "passive"))
      (node (ref "TP8") (pin "1") (pinfunction "1_1") (pintype "passive"))
      (node (ref "U5") (pin "6") (pinfunction "ANODE_6") (pintype "input"))
    )
    (net (code "41") (name "GND") (class "Default")
      (node (ref "C1") (pin "N") (pinfunction "N_N") (pintype "passive"))
      (node (ref "C20") (pin "1") (pinfunction "1_1") (pintype "passive"))
      (node (ref "C21") (pin "1") (pinfunction "1_1") (pintype "passive"))
      (node (ref "C22") (pin "1") (pinfunction "1_1") (pintype "passive"))
      (node (ref "C4") (pin "1") (pinfunction "1_1") (pintype "passive"))
      (node (ref "C6") (pin "N") (pinfunction "N_N") (pintype "passive"))
      (node (ref "C7") (pin "2") (pinfunction "2_2") (pintype "passive"))
      (node (ref "C8") (pin "2") (pinfunction "2_2") (pintype "passive"))
      (node (ref "CONN3") (pin "2") (pinfunction "2_2") (pintype "passive"))
      (node (ref "D5") (pin "1") (pinfunction "A_1") (pintype "passive"))
      (node (ref "J1") (pin "1") (pinfunction "1_1") (pintype "passive"))
      (node (ref "J1") (pin "2") (pinfunction "2_2") (pintype "passive"))
      (node (ref "J4") (pin "2") (pinfunction "2_2") (pintype "passive"))
      (node (ref "J5") (pin "1") (pinfunction "1_1") (pintype "passive"))
      (node (ref "J8") (pin "4") (pinfunction "4_4") (pintype "passive"))
      (node (ref "R20") (pin "1") (pinfunction "1_1") (pintype "passive"))
      (node (ref "TP7") (pin "1") (pinfunction "1_1") (pintype "passive"))
      (node (ref "U1") (pin "15") (pinfunction "0V1_15") (pintype "passive"))
      (node (ref "U1") (pin "16") (pinfunction "0V1_16") (pintype "passive"))
      (node (ref "U1") (pin "19") (pinfunction "THERM_19") (pintype "passive"))
      (node (ref "U2") (pin "2") (pinfunction "GND_2") (pintype "power_in"))
      (node (ref "U3") (pin "3") (pinfunction "3_3") (pintype "passive"))
      (node (ref "U4") (pin "3") (pinfunction "3_3") (pintype "passive"))
      (node (ref "U5") (pin "2") (pinfunction "GND_2") (pintype "power_in"))
      (node (ref "U6") (pin "3") (pinfunction "3_3") (pintype "passive"))
      (node (ref "U7") (pin "2") (pinfunction "2_2") (pintype "passive"))
      (node (ref "U9") (pin "2") (pinfunction "2_2") (pintype "passive"))
    )
    (net (code "42") (name "Net-(C9-Pad2)") (class "Default")
      (node (ref "C9") (pin "2") (pinfunction "2_2") (pintype "passive"))
      (node (ref "R10") (pin "1") (pinfunction "1_1") (pintype "passive"))
    )
    (net (code "43") (name "Net-(C10-Pad1)") (class "Default")
      (node (ref "C10") (pin "1") (pinfunction "1_1") (pintype "passive"))
      (node (ref "C11") (pin "1") (pinfunction "1_1") (pintype "passive"))
      (node (ref "C12") (pin "1") (pinfunction "1_1") (pintype "passive"))
      (node (ref "C17") (pin "2") (pinfunction "2_2") (pintype "passive"))
      (node (ref "C9") (pin "1") (pinfunction "1_1") (pintype "passive"))
    )
    (net (code "44") (name "Net-(C10-Pad2)") (class "Default")
      (node (ref "C10") (pin "2") (pinfunction "2_2") (pintype "passive"))
      (node (ref "R11") (pin "1") (pinfunction "1_1") (pintype "passive"))
    )
    (net (code "45") (name "Net-(C11-Pad2)") (class "Default")
      (node (ref "C11") (pin "2") (pinfunction "2_2") (pintype "passive"))
      (node (ref "R12") (pin "1") (pinfunction "1_1") (pintype "passive"))
    )
    (net (code "46") (name "Net-(C12-Pad2)") (class "Default")
      (node (ref "C12") (pin "2") (pinfunction "2_2") (pintype "passive"))
      (node (ref "R13") (pin "1") (pinfunction "1_1") (pintype "passive"))
    )
    (net (code "47") (name "Net-(C13-Pad1)") (class "Default")
      (node (ref "C13") (pin "1") (pinfunction "1_1") (pintype "passive"))
      (node (ref "C14") (pin "1") (pinfunction "1_1") (pintype "passive"))
      (node (ref "C15") (pin "1") (pinfunction "1_1") (pintype "passive"))
      (node (ref "C16") (pin "1") (pinfunction "1_1") (pintype "passive"))
      (node (ref "C18") (pin "2") (pinfunction "2_2") (pintype "passive"))
    )
    (net (code "48") (name "Net-(C13-Pad2)") (class "Default")
      (node (ref "C13") (pin "2") (pinfunction "2_2") (pintype "passive"))
      (node (ref "R14") (pin "1") (pinfunction "1_1") (pintype "passive"))
    )
    (net (code "49") (name "Net-(C14-Pad2)") (class "Default")
      (node (ref "C14") (pin "2") (pinfunction "2_2") (pintype "passive"))
      (node (ref "R15") (pin "1") (pinfunction "1_1") (pintype "passive"))
    )
    (net (code "50") (name "Net-(C15-Pad2)") (class "Default")
      (node (ref "C15") (pin "2") (pinfunction "2_2") (pintype "passive"))
      (node (ref "R16") (pin "1") (pinfunction "1_1") (pintype "passive"))
    )
    (net (code "51") (name "Net-(C16-Pad2)") (class "Default")
      (node (ref "C16") (pin "2") (pinfunction "2_2") (pintype "passive"))
      (node (ref "R17") (pin "1") (pinfunction "1_1") (pintype "passive"))
    )
    (net (code "52") (name "Net-(CONN3-Pad3)") (class "Default")
      (node (ref "CONN3") (pin "3") (pinfunction "3_3") (pintype "passive"))
      (node (ref "TP4") (pin "1") (pinfunction "1_1") (pintype "passive"))
    )
    (net (code "53") (name "Net-(D1-K)") (class "Default")
      (node (ref "D1") (pin "2") (pinfunction "K_2") (pintype "passive"))
      (node (ref "D2") (pin "1") (pinfunction "A_1") (pintype "passive"))
      (node (ref "R12") (pin "2") (pinfunction "2_2") (pintype "passive"))
      (node (ref "T1") (pin "18") (pinfunction "CX3_18") (pintype "passive"))
    )
    (net (code "54") (name "Net-(D3-A)") (class "Default")
      (node (ref "D3") (pin "1") (pinfunction "A_1") (pintype "passive"))
      (node (ref "D4") (pin "2") (pinfunction "K_2") (pintype "passive"))
      (node (ref "R13") (pin "2") (pinfunction "2_2") (pintype "passive"))
      (node (ref "T1") (pin "15") (pinfunction "CX4_15") (pintype "passive"))
    )
    (net (code "55") (name "Net-(D7-K)") (class "Default")
      (node (ref "D7") (pin "2") (pinfunction "K_2") (pintype "passive"))
      (node (ref "D8") (pin "1") (pinfunction "A_1") (pintype "passive"))
      (node (ref "R10") (pin "2") (pinfunction "2_2") (pintype "passive"))
      (node (ref "T1") (pin "24") (pinfunction "CX1_24") (pintype "passive"))
    )
    (net (code "56") (name "Net-(D10-K)") (class "Default")
      (node (ref "D10") (pin "2") (pinfunction "K_2") (pintype "passive"))
      (node (ref "D9") (pin "1") (pinfunction "A_1") (pintype "passive"))
      (node (ref "R11") (pin "2") (pinfunction "2_2") (pintype "passive"))
      (node (ref "T1") (pin "21") (pinfunction "CX2_21") (pintype "passive"))
    )
    (net (code "57") (name "Net-(D12-Pad2)") (class "Default")
      (node (ref "D12") (pin "2") (pinfunction "2_2") (pintype "passive"))
      (node (ref "R6") (pin "1") (pinfunction "1_1") (pintype "passive"))
    )
    (net (code "58") (name "Net-(D12-Pad4)") (class "Default")
      (node (ref "D12") (pin "4") (pinfunction "4_4") (pintype "passive"))
      (node (ref "R8") (pin "1") (pinfunction "1_1") (pintype "passive"))
    )
    (net (code "59") (name "Net-(D12-Pad6)") (class "Default")
      (node (ref "D12") (pin "6") (pinfunction "6_6") (pintype "passive"))
      (node (ref "R5") (pin "1") (pinfunction "1_1") (pintype "passive"))
    )
    (net (code "60") (name "Net-(FB1-Pad2)") (class "Default")
      (node (ref "FB1") (pin "2") (pinfunction "2_2") (pintype "passive"))
      (node (ref "R21") (pin "1") (pinfunction "1_1") (pintype "passive"))
    )
    (net (code "61") (name "Net-(FB2-Pad2)") (class "Default")
      (node (ref "FB2") (pin "2") (pinfunction "2_2") (pintype "passive"))
      (node (ref "R22") (pin "1") (pinfunction "1_1") (pintype "passive"))
    )
    (net (code "62") (name "Net-(J2-Pad2)") (class "Default")
      (node (ref "J2") (pin "2") (pinfunction "2_2") (pintype "passive"))
      (node (ref "R25") (pin "2") (pinfunction "2_2") (pintype "passive"))
    )
    (net (code "63") (name "Net-(J5-Pad2)") (class "Default")
      (node (ref "J5") (pin "2") (pinfunction "2_2") (pintype "passive"))
      (node (ref "R7") (pin "2") (pinfunction "2_2") (pintype "passive"))
    )
    (net (code "64") (name "Net-(J6-Pad1)") (class "Default")
      (node (ref "J6") (pin "1") (pinfunction "1_1") (pintype "passive"))
      (node (ref "R24") (pin "1") (pinfunction "1_1") (pintype "passive"))
      (node (ref "U9") (pin "4") (pinfunction "4_4") (pintype "passive"))
    )
    (net (code "65") (name "Net-(MP3-Pad1)") (class "Default")
      (node (ref "MP3") (pin "1") (pinfunction "1_1") (pintype "passive"))
      (node (ref "R1") (pin "1") (pinfunction "1_1") (pintype "passive"))
    )
    (net (code "66") (name "Net-(R18-Pad1)") (class "Default")
      (node (ref "R18") (pin "1") (pinfunction "1_1") (pintype "passive"))
      (node (ref "U7") (pin "4") (pinfunction "4_4") (pintype "passive"))
    )
    (net (code "67") (name "Net-(R19-Pad1)") (class "Default")
      (node (ref "R19") (pin "1") (pinfunction "1_1") (pintype "passive"))
      (node (ref "U8") (pin "4") (pinfunction "4_4") (pintype "passive"))
    )
    (net (code "68") (name "Net-(R25-Pad1)") (class "Default")
      (node (ref "R25") (pin "1") (pinfunction "1_1") (pintype "passive"))
      (node (ref "U9") (pin "1") (pinfunction "1_1") (pintype "passive"))
    )
    (net (code "69") (name "Net-(R26-Pad1)") (class "Default")
      (node (ref "R26") (pin "1") (pinfunction "1_1") (pintype "passive"))
      (node (ref "U8") (pin "1") (pinfunction "1_1") (pintype "passive"))
    )
    (net (code "70") (name "Net-(T1-CD1)") (class "Default")
      (node (ref "R17") (pin "2") (pinfunction "2_2") (pintype "passive"))
      (node (ref "T1") (pin "1") (pinfunction "CD1_1") (pintype "passive"))
    )
    (net (code "71") (name "Net-(T1-CD2)") (class "Default")
      (node (ref "R16") (pin "2") (pinfunction "2_2") (pintype "passive"))
      (node (ref "T1") (pin "4") (pinfunction "CD2_4") (pintype "passive"))
    )
    (net (code "72") (name "Net-(T1-CD3)") (class "Default")
      (node (ref "R15") (pin "2") (pinfunction "2_2") (pintype "passive"))
      (node (ref "T1") (pin "7") (pinfunction "CD3_7") (pintype "passive"))
    )
    (net (code "73") (name "Net-(T1-CD4)") (class "Default")
      (node (ref "R14") (pin "2") (pinfunction "2_2") (pintype "passive"))
      (node (ref "T1") (pin "10") (pinfunction "CD4_10") (pintype "passive"))
    )
    (net (code "74") (name "Net-(U1-PoH_En)") (class "Default")
      (node (ref "R2") (pin "1") (pinfunction "1_1") (pintype "passive"))
      (node (ref "U1") (pin "6") (pinfunction "PoH_En_6") (pintype "passive"))
    )
    (net (code "75") (name "Net-(U2-EN)") (class "Default")
      (node (ref "R3") (pin "1") (pinfunction "1_1") (pintype "passive"))
      (node (ref "TP2") (pin "1") (pinfunction "1_1") (pintype "passive"))
      (node (ref "U2") (pin "3") (pinfunction "EN_3") (pintype "input"))
    )
    (net (code "76") (name "Net-(U2-GATE)") (class "Default")
      (node (ref "Q1") (pin "4") (pinfunction "4_4") (pintype "passive"))
      (node (ref "U2") (pin "5") (pinfunction "GATE_5") (pintype "output"))
    )
    (net (code "77") (name "Net-(U2-VCAP)") (class "Default")
      (node (ref "C2") (pin "1") (pinfunction "1_1") (pintype "passive"))
      (node (ref "U2") (pin "1") (pinfunction "VCAP_1") (pintype "output"))
    )
    (net (code "78") (name "Net-(U5-EN)") (class "Default")
      (node (ref "R23") (pin "1") (pinfunction "1_1") (pintype "passive"))
      (node (ref "TP3") (pin "1") (pinfunction "1_1") (pintype "passive"))
      (node (ref "U5") (pin "3") (pinfunction "EN_3") (pintype "input"))
    )
    (net (code "79") (name "Net-(U5-GATE)") (class "Default")
      (node (ref "Q2") (pin "4") (pinfunction "4_4") (pintype "passive"))
      (node (ref "U5") (pin "5") (pinfunction "GATE_5") (pintype "output"))
    )
    (net (code "80") (name "Net-(U5-VCAP)") (class "Default")
      (node (ref "C19") (pin "1") (pinfunction "1_1") (pintype "passive"))
      (node (ref "U5") (pin "1") (pinfunction "VCAP_1") (pintype "output"))
    )
    (net (code "81") (name "VOUT") (class "Default")
      (node (ref "C1") (pin "P") (pinfunction "P_P") (pintype "passive"))
      (node (ref "C20") (pin "2") (pinfunction "2_2") (pintype "passive"))
      (node (ref "C4") (pin "2") (pinfunction "2_2") (pintype "passive"))
      (node (ref "J1") (pin "3") (pinfunction "3_3") (pintype "passive"))
      (node (ref "J1") (pin "4") (pinfunction "4_4") (pintype "passive"))
      (node (ref "Q1") (pin "5") (pinfunction "5_5") (pintype "passive"))
      (node (ref "Q1") (pin "6") (pinfunction "6_6") (pintype "passive"))
      (node (ref "Q1") (pin "7") (pinfunction "7_7") (pintype "passive"))
      (node (ref "Q1") (pin "8") (pinfunction "8_8") (pintype "passive"))
      (node (ref "Q2") (pin "5") (pinfunction "5_5") (pintype "passive"))
      (node (ref "Q2") (pin "6") (pinfunction "6_6") (pintype "passive"))
      (node (ref "Q2") (pin "7") (pinfunction "7_7") (pintype "passive"))
      (node (ref "Q2") (pin "8") (pinfunction "8_8") (pintype "passive"))
      (node (ref "TP6") (pin "1") (pinfunction "1_1") (pintype "passive"))
      (node (ref "U2") (pin "4") (pinfunction "CATHODE_4") (pintype "input"))
      (node (ref "U5") (pin "4") (pinfunction "CATHODE_4") (pintype "input"))
    )
    (net (code "82") (name "unconnected-(J4-Pad3)") (class "Default")
      (node (ref "J4") (pin "3") (pinfunction "3_3") (pintype "passive+no_connect"))
    )
    (net (code "83") (name "unconnected-(MP1-Pad1)") (class "Default")
      (node (ref "MP1") (pin "1") (pinfunction "1_1") (pintype "passive"))
    )
    (net (code "84") (name "unconnected-(MP2-Pad1)") (class "Default")
      (node (ref "MP2") (pin "1") (pinfunction "1_1") (pintype "passive"))
    )
    (net (code "85") (name "unconnected-(MP4-Pad1)") (class "Default")
      (node (ref "MP4") (pin "1") (pinfunction "1_1") (pintype "passive"))
    )
  )
)
